# EG8010.net
KiCad netlist of a schematic drawn in Altium Designer
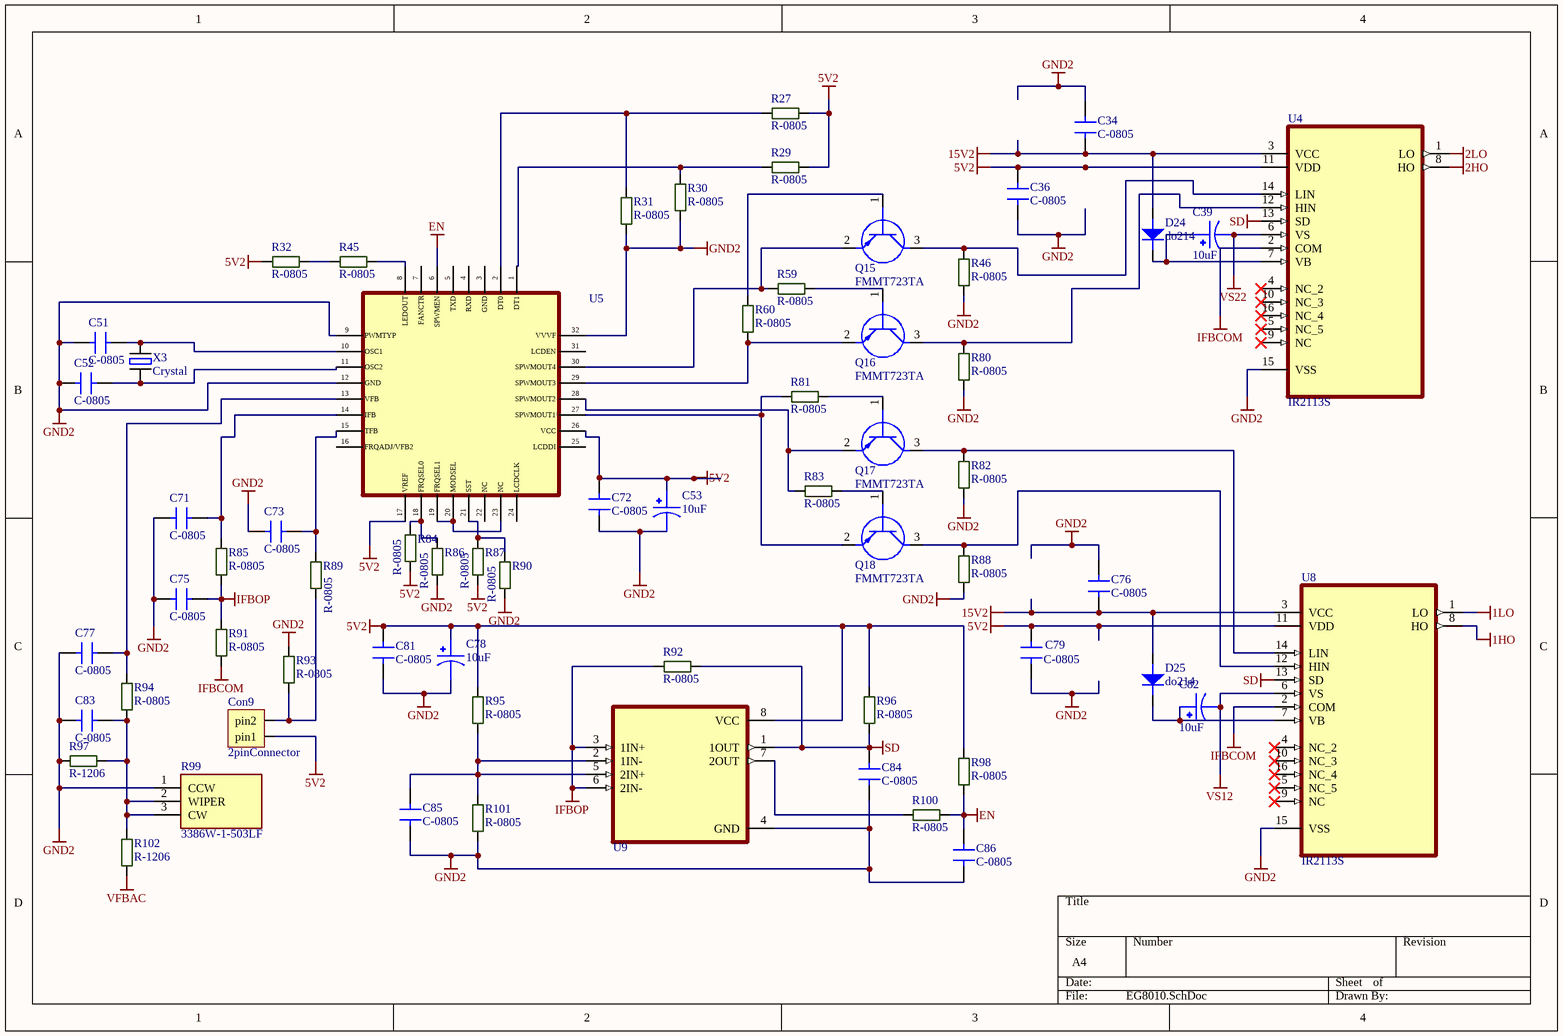
[diagram p0: EG8010.SchDoc]

(export (version "E")
  (design (tool "Eeschema 10.0.6"))
  (components
    (comp (ref "C34") (value "C-0805") (footprint "C-0805W") (libsource (lib "Schlib1") (part "C-0805")))
    (comp (ref "C36") (value "C-0805") (footprint "C-0805W") (libsource (lib "Schlib1") (part "C-0805")))
    (comp (ref "C39")
      (value "10uF")
      (footprint "CapSmdElc")
      (libsource (lib "PROJE") (part "100 uF Electr Cap"))
    )
    (comp (ref "C51") (value "C-0805") (footprint "C-0805W") (libsource (lib "Schlib1") (part "C-0805")))
    (comp (ref "C52") (value "C-0805") (footprint "C-0805W") (libsource (lib "Schlib1") (part "C-0805")))
    (comp (ref "C53")
      (value "10uF")
      (footprint "CapSmdElc")
      (libsource (lib "") (part "100 uF Electr Cap_1"))
    )
    (comp (ref "C71") (value "C-0805") (footprint "C-0805W") (libsource (lib "Schlib1") (part "C-0805")))
    (comp (ref "C72") (value "C-0805") (footprint "C-0805W") (libsource (lib "Schlib1") (part "C-0805")))
    (comp (ref "C73") (value "C-0805") (footprint "C-0805W") (libsource (lib "Schlib1") (part "C-0805")))
    (comp (ref "C75") (value "C-0805") (footprint "C-0805W") (libsource (lib "Schlib1") (part "C-0805")))
    (comp (ref "C76") (value "C-0805") (footprint "C-0805W") (libsource (lib "Schlib1") (part "C-0805")))
    (comp (ref "C77") (value "C-0805") (footprint "C-0805W") (libsource (lib "Schlib1") (part "C-0805")))
    (comp (ref "C78")
      (value "10uF")
      (footprint "CapSmdElc")
      (libsource (lib "") (part "100 uF Electr Cap_1"))
    )
    (comp (ref "C79") (value "C-0805") (footprint "C-0805W") (libsource (lib "Schlib1") (part "C-0805")))
    (comp (ref "C81") (value "C-0805") (footprint "C-0805W") (libsource (lib "Schlib1") (part "C-0805")))
    (comp (ref "C82")
      (value "10uF")
      (footprint "CapSmdElc")
      (libsource (lib "PROJE") (part "100 uF Electr Cap"))
    )
    (comp (ref "C83") (value "C-0805") (footprint "C-0805W") (libsource (lib "Schlib1") (part "C-0805")))
    (comp (ref "C84") (value "C-0805") (footprint "C-0805W") (libsource (lib "Schlib1") (part "C-0805")))
    (comp (ref "C85") (value "C-0805") (footprint "C-0805W") (libsource (lib "Schlib1") (part "C-0805")))
    (comp (ref "C86") (value "C-0805") (footprint "C-0805W") (libsource (lib "Schlib1") (part "C-0805")))
    (comp (ref "Con9")
      (value "2pinConnector")
      (footprint "2pinCon")
      (libsource (lib "Schlib1") (part "2pinConnector"))
    )
    (comp (ref "D24")
      (value "do214")
      (footprint "DO-214AC")
      (description "DIODE FAST SWITCHING Single 150mA 75V SMT SOD323")
      (libsource (lib "Schlib1") (part "do214"))
    )
    (comp (ref "D25")
      (value "do214")
      (footprint "DO-214AC")
      (description "DIODE FAST SWITCHING Single 150mA 75V SMT SOD323")
      (libsource (lib "Schlib1") (part "do214"))
    )
    (comp (ref "Q15")
      (value "FMMT723TA")
      (footprint "SamacSys:SOT96P240X100-3N")
      (description "Transistor BJT PNP")
      (fields (field (name "MOUSER PART NUMBER") "522-FMMT723TA"))
      (libsource (lib "*") (part "FMMT723TA"))
    )
    (comp (ref "Q16")
      (value "FMMT723TA")
      (footprint "SamacSys:SOT96P240X100-3N")
      (description "Transistor BJT PNP")
      (fields (field (name "MOUSER PART NUMBER") "522-FMMT723TA"))
      (libsource (lib "*") (part "FMMT723TA"))
    )
    (comp (ref "Q17")
      (value "FMMT723TA")
      (footprint "SamacSys:SOT96P240X100-3N")
      (description "Transistor BJT PNP")
      (fields (field (name "MOUSER PART NUMBER") "522-FMMT723TA"))
      (libsource (lib "*") (part "FMMT723TA"))
    )
    (comp (ref "Q18")
      (value "FMMT723TA")
      (footprint "SamacSys:SOT96P240X100-3N")
      (description "Transistor BJT PNP")
      (fields (field (name "MOUSER PART NUMBER") "522-FMMT723TA"))
      (libsource (lib "*") (part "FMMT723TA"))
    )
    (comp (ref "R27") (value "R-0805") (footprint "R-0805W") (libsource (lib "Schlib1") (part "R-0805")))
    (comp (ref "R29") (value "R-0805") (footprint "R-0805W") (libsource (lib "Schlib1") (part "R-0805")))
    (comp (ref "R30") (value "R-0805") (footprint "R-0805W") (libsource (lib "Schlib1") (part "R-0805")))
    (comp (ref "R31") (value "R-0805") (footprint "R-0805W") (libsource (lib "Schlib1") (part "R-0805")))
    (comp (ref "R32") (value "R-0805") (footprint "R-0805W") (libsource (lib "Schlib1") (part "R-0805")))
    (comp (ref "R45") (value "R-0805") (footprint "R-0805W") (libsource (lib "Schlib1") (part "R-0805")))
    (comp (ref "R46") (value "R-0805") (footprint "R-0805W") (libsource (lib "Schlib1") (part "R-0805")))
    (comp (ref "R59") (value "R-0805") (footprint "R-0805W") (libsource (lib "Schlib1") (part "R-0805")))
    (comp (ref "R60") (value "R-0805") (footprint "R-0805W") (libsource (lib "Schlib1") (part "R-0805")))
    (comp (ref "R80") (value "R-0805") (footprint "R-0805W") (libsource (lib "Schlib1") (part "R-0805")))
    (comp (ref "R81") (value "R-0805") (footprint "R-0805W") (libsource (lib "Schlib1") (part "R-0805")))
    (comp (ref "R82") (value "R-0805") (footprint "R-0805W") (libsource (lib "Schlib1") (part "R-0805")))
    (comp (ref "R83") (value "R-0805") (footprint "R-0805W") (libsource (lib "Schlib1") (part "R-0805")))
    (comp (ref "R84") (value "R-0805") (footprint "R-0805W") (libsource (lib "Schlib1") (part "R-0805")))
    (comp (ref "R85") (value "R-0805") (footprint "R-0805W") (libsource (lib "Schlib1") (part "R-0805")))
    (comp (ref "R86") (value "R-0805") (footprint "R-0805W") (libsource (lib "Schlib1") (part "R-0805")))
    (comp (ref "R87") (value "R-0805") (footprint "R-0805W") (libsource (lib "Schlib1") (part "R-0805")))
    (comp (ref "R88") (value "R-0805") (footprint "R-0805W") (libsource (lib "Schlib1") (part "R-0805")))
    (comp (ref "R89") (value "R-0805") (footprint "R-0805W") (libsource (lib "Schlib1") (part "R-0805")))
    (comp (ref "R90") (value "R-0805") (footprint "R-0805W") (libsource (lib "Schlib1") (part "R-0805")))
    (comp (ref "R91") (value "R-0805") (footprint "R-0805W") (libsource (lib "Schlib1") (part "R-0805")))
    (comp (ref "R92") (value "R-0805") (footprint "R-0805W") (libsource (lib "Schlib1") (part "R-0805")))
    (comp (ref "R93") (value "R-0805") (footprint "R-0805W") (libsource (lib "Schlib1") (part "R-0805")))
    (comp (ref "R94") (value "R-0805") (footprint "R-0805W") (libsource (lib "Schlib1") (part "R-0805")))
    (comp (ref "R95") (value "R-0805") (footprint "R-0805W") (libsource (lib "Schlib1") (part "R-0805")))
    (comp (ref "R96") (value "R-0805") (footprint "R-0805W") (libsource (lib "Schlib1") (part "R-0805")))
    (comp (ref "R97") (value "R-1206") (footprint "R-1206W") (libsource (lib "Schlib1") (part "R-1206")))
    (comp (ref "R98") (value "R-0805") (footprint "R-0805W") (libsource (lib "Schlib1") (part "R-0805")))
    (comp (ref "R99")
      (value "3386W-1-503LF")
      (footprint "SamacSys:3386W")
      (description "Resistor")
      (fields (field (name "MOUSER PART NUMBER") "652-3386W-1-503LF"))
      (libsource (lib "*") (part "3386W-1-503LF"))
    )
    (comp (ref "R100") (value "R-0805") (footprint "R-0805W") (libsource (lib "Schlib1") (part "R-0805")))
    (comp (ref "R101") (value "R-0805") (footprint "R-0805W") (libsource (lib "Schlib1") (part "R-0805")))
    (comp (ref "R102") (value "R-1206") (footprint "R-1206W") (libsource (lib "Schlib1") (part "R-1206")))
    (comp (ref "U4")
      (value "IR2113S")
      (footprint "SOIC127P1032X265-16N")
      (description "Half-Bridge Gate Driver IC Non-Inverting 16-SOIC")
      (fields (field (name "MF") "Infineon Technologies"))
      (libsource (lib "Schlib1") (part "IR2113S"))
    )
    (comp (ref "U5") (value "EG8010") (footprint "EG8010") (libsource (lib "Schlib1") (part "EG8010")))
    (comp (ref "U8")
      (value "IR2113S")
      (footprint "SOIC127P1032X265-16N")
      (description "Half-Bridge Gate Driver IC Non-Inverting 16-SOIC")
      (fields (field (name "MF") "Infineon Technologies"))
      (libsource (lib "Schlib1") (part "IR2113S"))
    )
    (comp (ref "U9")
      (value "LM393D")
      (footprint "SOIC127P600X175-8N")
      (description "Dual differential comparator, commercial grade 8-SOIC 0 to 70")
      (fields
        (field (name "MF") "Texas Instruments")
        (field (name "BUYPART") "https://www.snapeda.com/parts/LM393D/Texas%20Instruments/view-part/4806035/?ref=eda")
      )
      (libsource (lib "Schlib1") (part "LM393D"))
    )
    (comp (ref "X3")
      (value "Crystal")
      (footprint "crystal")
      (description "AS49SD-16M-FC160F3-TR")
      (libsource (lib "Schlib1") (part "Crystal"))
    )
  )
  (nets
    (net (code "1") (name "1HO") (class "Default")
      (node (ref "U8") (pin "8") (pinfunction "HO_8") (pintype "output"))
    )
    (net (code "2") (name "1LO") (class "Default")
      (node (ref "U8") (pin "1") (pinfunction "LO_1") (pintype "output"))
    )
    (net (code "3") (name "2HO") (class "Default")
      (node (ref "U4") (pin "8") (pinfunction "HO_8") (pintype "output"))
    )
    (net (code "4") (name "2LO") (class "Default")
      (node (ref "U4") (pin "1") (pinfunction "LO_1") (pintype "output"))
    )
    (net (code "5") (name "5V2") (class "Default")
      (node (ref "C36") (pin "2") (pinfunction "2_2") (pintype "passive"))
      (node (ref "C53") (pin "1") (pinfunction "1_1") (pintype "passive"))
      (node (ref "C72") (pin "2") (pinfunction "2_2") (pintype "passive"))
      (node (ref "C78") (pin "1") (pinfunction "1_1") (pintype "passive"))
      (node (ref "C79") (pin "2") (pinfunction "2_2") (pintype "passive"))
      (node (ref "C81") (pin "2") (pinfunction "2_2") (pintype "passive"))
      (node (ref "Con9") (pin "1") (pinfunction "pin1_1") (pintype "passive"))
      (node (ref "R27") (pin "2") (pinfunction "2_2") (pintype "passive"))
      (node (ref "R29") (pin "2") (pinfunction "2_2") (pintype "passive"))
      (node (ref "R32") (pin "1") (pinfunction "1_1") (pintype "passive"))
      (node (ref "R84") (pin "1") (pinfunction "1_1") (pintype "passive"))
      (node (ref "R87") (pin "1") (pinfunction "1_1") (pintype "passive"))
      (node (ref "R95") (pin "2") (pinfunction "2_2") (pintype "passive"))
      (node (ref "R96") (pin "2") (pinfunction "2_2") (pintype "passive"))
      (node (ref "R98") (pin "1") (pinfunction "1_1") (pintype "passive"))
      (node (ref "U4") (pin "11") (pinfunction "VDD_11") (pintype "power_in"))
      (node (ref "U5") (pin "17") (pinfunction "VREF_17") (pintype "passive"))
      (node (ref "U5") (pin "26") (pinfunction "VCC_26") (pintype "passive"))
      (node (ref "U8") (pin "11") (pinfunction "VDD_11") (pintype "power_in"))
      (node (ref "U9") (pin "8") (pinfunction "VCC_8") (pintype "power_in"))
    )
    (net (code "6") (name "15V2") (class "Default")
      (node (ref "C34") (pin "2") (pinfunction "2_2") (pintype "passive"))
      (node (ref "C76") (pin "2") (pinfunction "2_2") (pintype "passive"))
      (node (ref "D24") (pin "a") (pinfunction "a_a") (pintype "passive"))
      (node (ref "D25") (pin "a") (pinfunction "a_a") (pintype "passive"))
      (node (ref "U4") (pin "3") (pinfunction "VCC_3") (pintype "power_in"))
      (node (ref "U8") (pin "3") (pinfunction "VCC_3") (pintype "power_in"))
    )
    (net (code "7") (name "EN") (class "Default")
      (node (ref "C86") (pin "2") (pinfunction "2_2") (pintype "passive"))
      (node (ref "R100") (pin "1") (pinfunction "1_1") (pintype "passive"))
      (node (ref "R98") (pin "2") (pinfunction "2_2") (pintype "passive"))
      (node (ref "U5") (pin "6") (pinfunction "SPWMEN_6") (pintype "passive"))
    )
    (net (code "8") (name "GND2") (class "Default")
      (node (ref "C34") (pin "1") (pinfunction "1_1") (pintype "passive"))
      (node (ref "C36") (pin "1") (pinfunction "1_1") (pintype "passive"))
      (node (ref "C51") (pin "1") (pinfunction "1_1") (pintype "passive"))
      (node (ref "C52") (pin "1") (pinfunction "1_1") (pintype "passive"))
      (node (ref "C53") (pin "2") (pinfunction "2_2") (pintype "passive"))
      (node (ref "C71") (pin "1") (pinfunction "1_1") (pintype "passive"))
      (node (ref "C72") (pin "1") (pinfunction "1_1") (pintype "passive"))
      (node (ref "C73") (pin "1") (pinfunction "1_1") (pintype "passive"))
      (node (ref "C75") (pin "1") (pinfunction "1_1") (pintype "passive"))
      (node (ref "C76") (pin "1") (pinfunction "1_1") (pintype "passive"))
      (node (ref "C77") (pin "1") (pinfunction "1_1") (pintype "passive"))
      (node (ref "C78") (pin "2") (pinfunction "2_2") (pintype "passive"))
      (node (ref "C79") (pin "1") (pinfunction "1_1") (pintype "passive"))
      (node (ref "C81") (pin "1") (pinfunction "1_1") (pintype "passive"))
      (node (ref "C83") (pin "1") (pinfunction "1_1") (pintype "passive"))
      (node (ref "C84") (pin "1") (pinfunction "1_1") (pintype "passive"))
      (node (ref "C85") (pin "1") (pinfunction "1_1") (pintype "passive"))
      (node (ref "C86") (pin "1") (pinfunction "1_1") (pintype "passive"))
      (node (ref "R101") (pin "1") (pinfunction "1_1") (pintype "passive"))
      (node (ref "R30") (pin "1") (pinfunction "1_1") (pintype "passive"))
      (node (ref "R31") (pin "1") (pinfunction "1_1") (pintype "passive"))
      (node (ref "R46") (pin "2") (pinfunction "2_2") (pintype "passive"))
      (node (ref "R80") (pin "2") (pinfunction "2_2") (pintype "passive"))
      (node (ref "R82") (pin "2") (pinfunction "2_2") (pintype "passive"))
      (node (ref "R86") (pin "1") (pinfunction "1_1") (pintype "passive"))
      (node (ref "R88") (pin "2") (pinfunction "2_2") (pintype "passive"))
      (node (ref "R90") (pin "1") (pinfunction "1_1") (pintype "passive"))
      (node (ref "R93") (pin "2") (pinfunction "2_2") (pintype "passive"))
      (node (ref "R97") (pin "2") (pinfunction "2_2") (pintype "passive"))
      (node (ref "R99") (pin "1") (pinfunction "CCW_1") (pintype "passive"))
      (node (ref "U4") (pin "15") (pinfunction "VSS_15") (pintype "passive"))
      (node (ref "U5") (pin "12") (pinfunction "GND_12") (pintype "passive"))
      (node (ref "U5") (pin "32") (pinfunction "VVVF_32") (pintype "passive"))
      (node (ref "U5") (pin "9") (pinfunction "PWMTYP_9") (pintype "passive"))
      (node (ref "U8") (pin "15") (pinfunction "VSS_15") (pintype "passive"))
      (node (ref "U9") (pin "4") (pinfunction "GND_4") (pintype "power_in"))
    )
    (net (code "9") (name "IFBCOM") (class "Default")
      (node (ref "R91") (pin "1") (pinfunction "1_1") (pintype "passive"))
      (node (ref "U4") (pin "2") (pinfunction "COM_2") (pintype "input"))
      (node (ref "U8") (pin "2") (pinfunction "COM_2") (pintype "input"))
    )
    (net (code "10") (name "IFBOP") (class "Default")
      (node (ref "C75") (pin "2") (pinfunction "2_2") (pintype "passive"))
      (node (ref "R85") (pin "1") (pinfunction "1_1") (pintype "passive"))
      (node (ref "R91") (pin "2") (pinfunction "2_2") (pintype "passive"))
      (node (ref "R92") (pin "1") (pinfunction "1_1") (pintype "passive"))
      (node (ref "U9") (pin "3") (pinfunction "1IN+_3") (pintype "input"))
      (node (ref "U9") (pin "6") (pinfunction "2IN-_6") (pintype "input"))
    )
    (net (code "11") (name "Net-(Con9-pin2)") (class "Default")
      (node (ref "Con9") (pin "2") (pinfunction "pin2_2") (pintype "passive"))
      (node (ref "R89") (pin "1") (pinfunction "1_1") (pintype "passive"))
      (node (ref "R93") (pin "1") (pinfunction "1_1") (pintype "passive"))
    )
    (net (code "12") (name "Net-(Q15-B)") (class "Default")
      (node (ref "Q15") (pin "1") (pinfunction "B_1") (pintype "passive"))
      (node (ref "R60") (pin "2") (pinfunction "2_2") (pintype "passive"))
    )
    (net (code "13") (name "Net-(Q15-C)") (class "Default")
      (node (ref "Q15") (pin "3") (pinfunction "C_3") (pintype "passive"))
      (node (ref "R46") (pin "1") (pinfunction "1_1") (pintype "passive"))
      (node (ref "U4") (pin "14") (pinfunction "LIN_14") (pintype "input"))
    )
    (net (code "14") (name "Net-(Q15-E)") (class "Default")
      (node (ref "Q15") (pin "2") (pinfunction "E_2") (pintype "passive"))
      (node (ref "R59") (pin "2") (pinfunction "2_2") (pintype "passive"))
      (node (ref "U5") (pin "30") (pinfunction "SPWMOUT4_30") (pintype "passive"))
    )
    (net (code "15") (name "Net-(Q16-B)") (class "Default")
      (node (ref "Q16") (pin "1") (pinfunction "B_1") (pintype "passive"))
      (node (ref "R59") (pin "1") (pinfunction "1_1") (pintype "passive"))
    )
    (net (code "16") (name "Net-(Q16-C)") (class "Default")
      (node (ref "Q16") (pin "3") (pinfunction "C_3") (pintype "passive"))
      (node (ref "R80") (pin "1") (pinfunction "1_1") (pintype "passive"))
      (node (ref "U4") (pin "12") (pinfunction "HIN_12") (pintype "input"))
    )
    (net (code "17") (name "Net-(Q16-E)") (class "Default")
      (node (ref "Q16") (pin "2") (pinfunction "E_2") (pintype "passive"))
      (node (ref "R60") (pin "1") (pinfunction "1_1") (pintype "passive"))
      (node (ref "U5") (pin "29") (pinfunction "SPWMOUT3_29") (pintype "passive"))
    )
    (net (code "18") (name "Net-(Q17-B)") (class "Default")
      (node (ref "Q17") (pin "1") (pinfunction "B_1") (pintype "passive"))
      (node (ref "R81") (pin "1") (pinfunction "1_1") (pintype "passive"))
    )
    (net (code "19") (name "Net-(Q17-C)") (class "Default")
      (node (ref "Q17") (pin "3") (pinfunction "C_3") (pintype "passive"))
      (node (ref "R82") (pin "1") (pinfunction "1_1") (pintype "passive"))
      (node (ref "U8") (pin "14") (pinfunction "LIN_14") (pintype "input"))
    )
    (net (code "20") (name "Net-(Q17-E)") (class "Default")
      (node (ref "Q17") (pin "2") (pinfunction "E_2") (pintype "passive"))
      (node (ref "R83") (pin "2") (pinfunction "2_2") (pintype "passive"))
      (node (ref "U5") (pin "28") (pinfunction "SPWMOUT2_28") (pintype "passive"))
    )
    (net (code "21") (name "Net-(Q18-B)") (class "Default")
      (node (ref "Q18") (pin "1") (pinfunction "B_1") (pintype "passive"))
      (node (ref "R83") (pin "1") (pinfunction "1_1") (pintype "passive"))
    )
    (net (code "22") (name "Net-(Q18-C)") (class "Default")
      (node (ref "Q18") (pin "3") (pinfunction "C_3") (pintype "passive"))
      (node (ref "R88") (pin "1") (pinfunction "1_1") (pintype "passive"))
      (node (ref "U8") (pin "12") (pinfunction "HIN_12") (pintype "input"))
    )
    (net (code "23") (name "Net-(Q18-E)") (class "Default")
      (node (ref "Q18") (pin "2") (pinfunction "E_2") (pintype "passive"))
      (node (ref "R81") (pin "2") (pinfunction "2_2") (pintype "passive"))
      (node (ref "U5") (pin "27") (pinfunction "SPWMOUT1_27") (pintype "passive"))
    )
    (net (code "24") (name "Net-(R32-Pad2)") (class "Default")
      (node (ref "R32") (pin "2") (pinfunction "2_2") (pintype "passive"))
      (node (ref "R45") (pin "1") (pinfunction "1_1") (pintype "passive"))
    )
    (net (code "25") (name "Net-(R99-CW)") (class "Default")
      (node (ref "C83") (pin "2") (pinfunction "2_2") (pintype "passive"))
      (node (ref "R102") (pin "2") (pinfunction "2_2") (pintype "passive"))
      (node (ref "R94") (pin "1") (pinfunction "1_1") (pintype "passive"))
      (node (ref "R97") (pin "1") (pinfunction "1_1") (pintype "passive"))
      (node (ref "R99") (pin "2") (pinfunction "WIPER_2") (pintype "passive"))
      (node (ref "R99") (pin "3") (pinfunction "CW_3") (pintype "passive"))
    )
    (net (code "26") (name "Net-(U4-VB)") (class "Default")
      (node (ref "C39") (pin "1") (pinfunction "1_1") (pintype "passive"))
      (node (ref "D24") (pin "k") (pinfunction "k_k") (pintype "passive"))
      (node (ref "U4") (pin "7") (pinfunction "VB_7") (pintype "input"))
    )
    (net (code "27") (name "Net-(U5-DT0)") (class "Default")
      (node (ref "R27") (pin "1") (pinfunction "1_1") (pintype "passive"))
      (node (ref "R31") (pin "2") (pinfunction "2_2") (pintype "passive"))
      (node (ref "U5") (pin "2") (pinfunction "DT0_2") (pintype "passive"))
    )
    (net (code "28") (name "Net-(U5-DT1)") (class "Default")
      (node (ref "R29") (pin "1") (pinfunction "1_1") (pintype "passive"))
      (node (ref "R30") (pin "2") (pinfunction "2_2") (pintype "passive"))
      (node (ref "U5") (pin "1") (pinfunction "DT1_1") (pintype "passive"))
    )
    (net (code "29") (name "Net-(U5-FRQSEL0)") (class "Default")
      (node (ref "R84") (pin "2") (pinfunction "2_2") (pintype "passive"))
      (node (ref "R86") (pin "2") (pinfunction "2_2") (pintype "passive"))
      (node (ref "U5") (pin "18") (pinfunction "FRQSEL0_18") (pintype "passive"))
    )
    (net (code "30") (name "Net-(U5-FRQSEL1)") (class "Default")
      (node (ref "U5") (pin "19") (pinfunction "FRQSEL1_19") (pintype "passive"))
      (node (ref "U5") (pin "20") (pinfunction "MODSEL_20") (pintype "passive"))
      (node (ref "U5") (pin "23") (pinfunction "NC_23") (pintype "passive"))
    )
    (net (code "31") (name "Net-(U5-IFB)") (class "Default")
      (node (ref "C71") (pin "2") (pinfunction "2_2") (pintype "passive"))
      (node (ref "R85") (pin "2") (pinfunction "2_2") (pintype "passive"))
      (node (ref "U5") (pin "14") (pinfunction "IFB_14") (pintype "passive"))
    )
    (net (code "32") (name "Net-(U5-LEDOUT)") (class "Default")
      (node (ref "R45") (pin "2") (pinfunction "2_2") (pintype "passive"))
      (node (ref "U5") (pin "8") (pinfunction "LEDOUT_8") (pintype "passive"))
    )
    (net (code "33") (name "Net-(U5-OSC1)") (class "Default")
      (node (ref "C51") (pin "2") (pinfunction "2_2") (pintype "passive"))
      (node (ref "U5") (pin "10") (pinfunction "OSC1_10") (pintype "passive"))
      (node (ref "X3") (pin "1") (pinfunction "1_1") (pintype "passive"))
    )
    (net (code "34") (name "Net-(U5-OSC2)") (class "Default")
      (node (ref "C52") (pin "2") (pinfunction "2_2") (pintype "passive"))
      (node (ref "U5") (pin "11") (pinfunction "OSC2_11") (pintype "passive"))
      (node (ref "X3") (pin "2") (pinfunction "2_2") (pintype "passive"))
    )
    (net (code "35") (name "Net-(U5-SST)") (class "Default")
      (node (ref "R87") (pin "2") (pinfunction "2_2") (pintype "passive"))
      (node (ref "R90") (pin "2") (pinfunction "2_2") (pintype "passive"))
      (node (ref "U5") (pin "21") (pinfunction "SST_21") (pintype "passive"))
    )
    (net (code "36") (name "Net-(U5-TFB)") (class "Default")
      (node (ref "C73") (pin "2") (pinfunction "2_2") (pintype "passive"))
      (node (ref "R89") (pin "2") (pinfunction "2_2") (pintype "passive"))
      (node (ref "U5") (pin "15") (pinfunction "TFB_15") (pintype "passive"))
    )
    (net (code "37") (name "Net-(U5-VFB)") (class "Default")
      (node (ref "C77") (pin "2") (pinfunction "2_2") (pintype "passive"))
      (node (ref "R94") (pin "2") (pinfunction "2_2") (pintype "passive"))
      (node (ref "U5") (pin "13") (pinfunction "VFB_13") (pintype "passive"))
    )
    (net (code "38") (name "Net-(U8-VB)") (class "Default")
      (node (ref "C82") (pin "1") (pinfunction "1_1") (pintype "passive"))
      (node (ref "D25") (pin "k") (pinfunction "k_k") (pintype "passive"))
      (node (ref "U8") (pin "7") (pinfunction "VB_7") (pintype "input"))
    )
    (net (code "39") (name "Net-(U9-1IN-)") (class "Default")
      (node (ref "C85") (pin "2") (pinfunction "2_2") (pintype "passive"))
      (node (ref "R101") (pin "2") (pinfunction "2_2") (pintype "passive"))
      (node (ref "R95") (pin "1") (pinfunction "1_1") (pintype "passive"))
      (node (ref "U9") (pin "2") (pinfunction "1IN-_2") (pintype "input"))
      (node (ref "U9") (pin "5") (pinfunction "2IN+_5") (pintype "input"))
    )
    (net (code "40") (name "Net-(U9-2OUT)") (class "Default")
      (node (ref "R100") (pin "2") (pinfunction "2_2") (pintype "passive"))
      (node (ref "U9") (pin "7") (pinfunction "2OUT_7") (pintype "output"))
    )
    (net (code "41") (name "SD") (class "Default")
      (node (ref "C84") (pin "2") (pinfunction "2_2") (pintype "passive"))
      (node (ref "R92") (pin "2") (pinfunction "2_2") (pintype "passive"))
      (node (ref "R96") (pin "1") (pinfunction "1_1") (pintype "passive"))
      (node (ref "U4") (pin "13") (pinfunction "SD_13") (pintype "input"))
      (node (ref "U8") (pin "13") (pinfunction "SD_13") (pintype "input"))
      (node (ref "U9") (pin "1") (pinfunction "1OUT_1") (pintype "output"))
    )
    (net (code "42") (name "VFBAC") (class "Default")
      (node (ref "R102") (pin "1") (pinfunction "1_1") (pintype "passive"))
    )
    (net (code "43") (name "VS12") (class "Default")
      (node (ref "C82") (pin "2") (pinfunction "2_2") (pintype "passive"))
      (node (ref "U8") (pin "6") (pinfunction "VS_6") (pintype "input"))
    )
    (net (code "44") (name "VS22") (class "Default")
      (node (ref "C39") (pin "2") (pinfunction "2_2") (pintype "passive"))
      (node (ref "U4") (pin "6") (pinfunction "VS_6") (pintype "input"))
    )
    (net (code "45") (name "unconnected-(U4-NC-Pad9)") (class "Default")
      (node (ref "U4") (pin "9") (pinfunction "NC_9") (pintype "input+no_connect"))
    )
    (net (code "46") (name "unconnected-(U4-NC_2-Pad4)") (class "Default")
      (node (ref "U4") (pin "4") (pinfunction "NC_2_4") (pintype "input+no_connect"))
    )
    (net (code "47") (name "unconnected-(U4-NC_3-Pad10)") (class "Default")
      (node (ref "U4") (pin "10") (pinfunction "NC_3_10") (pintype "input+no_connect"))
    )
    (net (code "48") (name "unconnected-(U4-NC_4-Pad16)") (class "Default")
      (node (ref "U4") (pin "16") (pinfunction "NC_4_16") (pintype "input+no_connect"))
    )
    (net (code "49") (name "unconnected-(U4-NC_5-Pad5)") (class "Default")
      (node (ref "U4") (pin "5") (pinfunction "NC_5_5") (pintype "input+no_connect"))
    )
    (net (code "50") (name "unconnected-(U5-FANCTR-Pad7)") (class "Default")
      (node (ref "U5") (pin "7") (pinfunction "FANCTR_7") (pintype "passive"))
    )
    (net (code "51") (name "unconnected-(U5-FRQADJ{slash}VFB2-Pad16)") (class "Default")
      (node (ref "U5") (pin "16") (pinfunction "FRQADJ/VFB2_16") (pintype "passive"))
    )
    (net (code "52") (name "unconnected-(U5-GND-Pad3)") (class "Default")
      (node (ref "U5") (pin "3") (pinfunction "GND_3") (pintype "passive"))
    )
    (net (code "53") (name "unconnected-(U5-LCDCLK-Pad24)") (class "Default")
      (node (ref "U5") (pin "24") (pinfunction "LCDCLK_24") (pintype "passive"))
    )
    (net (code "54") (name "unconnected-(U5-LCDDI-Pad25)") (class "Default")
      (node (ref "U5") (pin "25") (pinfunction "LCDDI_25") (pintype "passive"))
    )
    (net (code "55") (name "unconnected-(U5-LCDEN-Pad31)") (class "Default")
      (node (ref "U5") (pin "31") (pinfunction "LCDEN_31") (pintype "passive"))
    )
    (net (code "56") (name "unconnected-(U5-NC-Pad22)") (class "Default")
      (node (ref "U5") (pin "22") (pinfunction "NC_22") (pintype "passive"))
    )
    (net (code "57") (name "unconnected-(U5-RXD-Pad4)") (class "Default")
      (node (ref "U5") (pin "4") (pinfunction "RXD_4") (pintype "passive"))
    )
    (net (code "58") (name "unconnected-(U5-TXD-Pad5)") (class "Default")
      (node (ref "U5") (pin "5") (pinfunction "TXD_5") (pintype "passive"))
    )
    (net (code "59") (name "unconnected-(U8-NC-Pad9)") (class "Default")
      (node (ref "U8") (pin "9") (pinfunction "NC_9") (pintype "input+no_connect"))
    )
    (net (code "60") (name "unconnected-(U8-NC_2-Pad4)") (class "Default")
      (node (ref "U8") (pin "4") (pinfunction "NC_2_4") (pintype "input+no_connect"))
    )
    (net (code "61") (name "unconnected-(U8-NC_3-Pad10)") (class "Default")
      (node (ref "U8") (pin "10") (pinfunction "NC_3_10") (pintype "input+no_connect"))
    )
    (net (code "62") (name "unconnected-(U8-NC_4-Pad16)") (class "Default")
      (node (ref "U8") (pin "16") (pinfunction "NC_4_16") (pintype "input+no_connect"))
    )
    (net (code "63") (name "unconnected-(U8-NC_5-Pad5)") (class "Default")
      (node (ref "U8") (pin "5") (pinfunction "NC_5_5") (pintype "input+no_connect"))
    )
  )
)
